# Power_Distribution_-_Front_Lights.net
KiCad netlist of a schematic drawn in Altium Designer
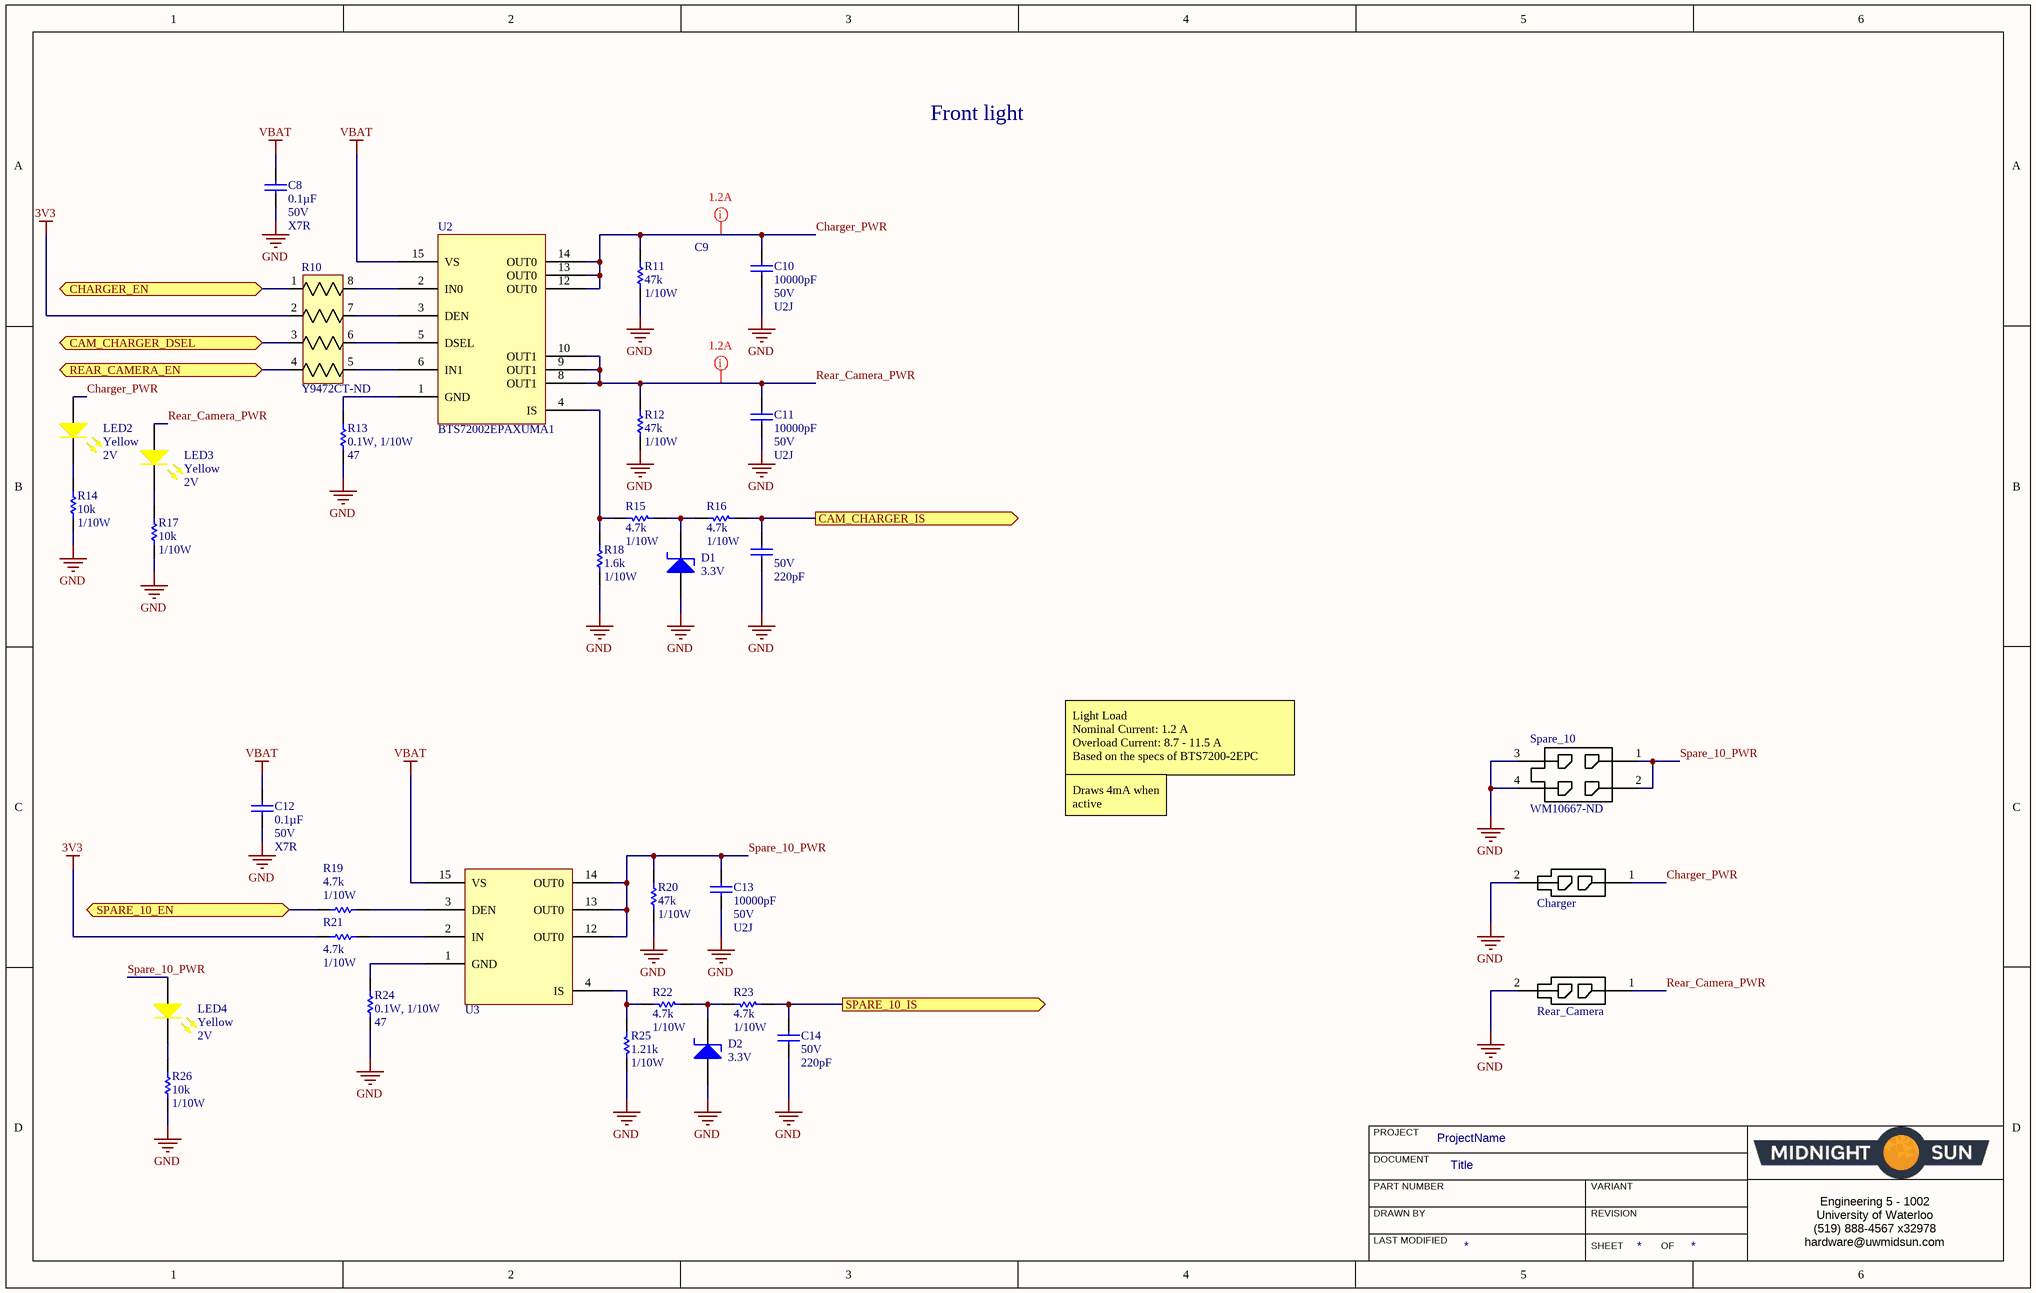
[diagram p0: Power Distribution - Front Lights.SchDoc]

(export (version "E")
  (design (tool "Eeschema 10.0.6"))
  (components
    (comp (ref "C8")
      (value "CAP CER 0.1UF 50V 10% X7R 0603")
      (footprint "CAP, 0603")
      (description "0.10µF ±10% 50V Ceramic Capacitor X7R 0603 (1608 Metric)")
      (fields
        (field (name "TOLERANCE") "±10%")
        (field (name "CAPACITANCE") "0.1µF")
        (field (name "VOLTAGE") "50V")
        (field (name "TEMPERATURE COEFFICIENT") "X7R")
      )
      (libsource (lib "Schematic Diagrams") (part "CAP CER 0.1UF 50V 10% X7R 0603"))
    )
    (comp (ref "C9")
      (value "CAP CER 220PF 50V C0G/NP0 0603")
      (footprint "CAP, 0603")
      (description "220pF ±5% 50V Ceramic Capacitor C0G, NP0 0603 (1608 Metric)")
      (fields
        (field (name "MANUFACTURER") "KEMET")
        (field (name "TOLERANCE") "5%")
        (field (name "VOLTAGE RATING") "50V")
        (field (name "CAPACITANCE") "220pF")
      )
      (libsource (lib "Schematic Diagrams") (part "CAP CER 220PF 50V C0G/NP0 0603"))
    )
    (comp (ref "C10")
      (value "CAP CER 10nF 50V 5% X7R 0603")
      (footprint "CAP, 0603")
      (description "10000pF ±5% 50V Ceramic Capacitor U2J 0603 (1608 Metric)")
      (fields
        (field (name "TOLERANCE") "±5%")
        (field (name "CAPACITANCE") "10000pF")
        (field (name "VOLTAGE") "50V")
        (field (name "TEMPERATURE COEFFICIENT") "U2J")
      )
      (libsource (lib "Schematic Diagrams") (part "CAP CER 10nF 50V 5% X7R 0603"))
    )
    (comp (ref "C11")
      (value "CAP CER 10nF 50V 5% X7R 0603")
      (footprint "CAP, 0603")
      (description "10000pF ±5% 50V Ceramic Capacitor U2J 0603 (1608 Metric)")
      (fields
        (field (name "TOLERANCE") "±5%")
        (field (name "CAPACITANCE") "10000pF")
        (field (name "VOLTAGE") "50V")
        (field (name "TEMPERATURE COEFFICIENT") "U2J")
      )
      (libsource (lib "Schematic Diagrams") (part "CAP CER 10nF 50V 5% X7R 0603"))
    )
    (comp (ref "C12")
      (value "CAP CER 0.1UF 50V 10% X7R 0603")
      (footprint "CAP, 0603")
      (description "0.10µF ±10% 50V Ceramic Capacitor X7R 0603 (1608 Metric)")
      (fields
        (field (name "TOLERANCE") "±10%")
        (field (name "CAPACITANCE") "0.1µF")
        (field (name "VOLTAGE") "50V")
        (field (name "TEMPERATURE COEFFICIENT") "X7R")
      )
      (libsource (lib "Schematic Diagrams") (part "CAP CER 0.1UF 50V 10% X7R 0603"))
    )
    (comp (ref "C13")
      (value "CAP CER 10nF 50V 5% X7R 0603")
      (footprint "CAP, 0603")
      (description "10000pF ±5% 50V Ceramic Capacitor U2J 0603 (1608 Metric)")
      (fields
        (field (name "TOLERANCE") "±5%")
        (field (name "CAPACITANCE") "10000pF")
        (field (name "VOLTAGE") "50V")
        (field (name "TEMPERATURE COEFFICIENT") "U2J")
      )
      (libsource (lib "Schematic Diagrams") (part "CAP CER 10nF 50V 5% X7R 0603"))
    )
    (comp (ref "C14")
      (value "CAP CER 220PF 50V C0G/NP0 0603")
      (footprint "CAP, 0603")
      (description "220pF ±5% 50V Ceramic Capacitor C0G, NP0 0603 (1608 Metric)")
      (fields
        (field (name "MANUFACTURER") "KEMET")
        (field (name "TOLERANCE") "5%")
        (field (name "VOLTAGE RATING") "50V")
        (field (name "CAPACITANCE") "220pF")
      )
      (libsource (lib "Schematic Diagrams") (part "CAP CER 220PF 50V C0G/NP0 0603"))
    )
    (comp (ref "Charger")
      (value "CONN 2POS MICRO-FIT 3mm")
      (footprint "CONN, 2POS MICRO-FIT")
      (description "Connector Header Through Hole 2 position")
      (fields (field (name "MANUFACTURER") "Molex") (field (name "MANUFACTURER PART NUMBER") "43045-0227"))
      (libsource (lib "Schematic Diagrams") (part "CONN 2POS MICRO-FIT 3mm"))
    )
    (comp (ref "D1")
      (value "DIODE ZENER 3.3V 200MW SOD323")
      (footprint "sod-323")
      (description "Zener Diode 3.3V 200mW ±5% Surface Mount SOD-323")
      (fields (field (name "VOLTAGE") "3.3V"))
      (libsource (lib "Schematic Diagrams") (part "DIODE ZENER 3.3V 200MW SOD323"))
    )
    (comp (ref "D2")
      (value "DIODE ZENER 3.3V 200MW SOD323")
      (footprint "sod-323")
      (description "Zener Diode 3.3V 200mW ±5% Surface Mount SOD-323")
      (fields (field (name "VOLTAGE") "3.3V"))
      (libsource (lib "Schematic Diagrams") (part "DIODE ZENER 3.3V 200MW SOD323"))
    )
    (comp (ref "LED2")
      (value "LED YELLOW CLEAR 2.1V 0603")
      (footprint "LED_0603")
      (description "Yellow 590nm LED Indication - Discrete 2V 0603 (1608 Metric)")
      (fields
        (field (name "MANUFACTURER") "Wurth Electronics Inc.")
        (field (name "MANUFACTURER PART NUMBER") "150060YS75000")
        (field (name "COLOR") "Yellow")
        (field (name "VOLTAGE - FORWARD (VF) (TYP)") "2V")
      )
      (libsource (lib "Schematic Diagrams") (part "LED YELLOW CLEAR 2.1V 0603"))
    )
    (comp (ref "LED3")
      (value "LED YELLOW CLEAR 2.1V 0603")
      (footprint "LED_0603")
      (description "Yellow 590nm LED Indication - Discrete 2V 0603 (1608 Metric)")
      (fields
        (field (name "MANUFACTURER") "Wurth Electronics Inc.")
        (field (name "MANUFACTURER PART NUMBER") "150060YS75000")
        (field (name "COLOR") "Yellow")
        (field (name "VOLTAGE - FORWARD (VF) (TYP)") "2V")
      )
      (libsource (lib "Schematic Diagrams") (part "LED YELLOW CLEAR 2.1V 0603"))
    )
    (comp (ref "LED4")
      (value "LED YELLOW CLEAR 2.1V 0603")
      (footprint "LED_0603")
      (description "Yellow 590nm LED Indication - Discrete 2V 0603 (1608 Metric)")
      (fields
        (field (name "MANUFACTURER") "Wurth Electronics Inc.")
        (field (name "MANUFACTURER PART NUMBER") "150060YS75000")
        (field (name "COLOR") "Yellow")
        (field (name "VOLTAGE - FORWARD (VF) (TYP)") "2V")
      )
      (libsource (lib "Schematic Diagrams") (part "LED YELLOW CLEAR 2.1V 0603"))
    )
    (comp (ref "R10")
      (value "RES ARRAY 4 RES 4.7K OHM 1206")
      (footprint "RES ARRAY 4RES 1206")
      (fields (field (name "TOLERANCE") "±5%") (field (name "SUPPLIER PART NUMBER 1") "Y9472CT-ND"))
      (libsource (lib "Schematic Diagrams") (part "RES ARRAY 4 RES 4.7K OHM 1206"))
    )
    (comp (ref "R11")
      (value "RES 47K OHM 1% 1/10W 0603")
      (footprint "RES, 0603")
      (description "47 kOhms ±1% 0.1W, 1/10W Chip Resistor 0603 (1608 Metric) Automotive AEC-Q200 Thick Film")
      (fields
        (field (name "MANUFACTURER") "Panasonic")
        (field (name "MANUFACTURER PART NUMBER") "ERJ3EKF4702V")
        (field (name "RESISTANCE") "47k")
        (field (name "POWER RATING") "1/10W")
      )
      (libsource (lib "Schematic Diagrams") (part "RES 47K OHM 1% 1/10W 0603"))
    )
    (comp (ref "R12")
      (value "RES 47K OHM 1% 1/10W 0603")
      (footprint "RES, 0603")
      (description "47 kOhms ±1% 0.1W, 1/10W Chip Resistor 0603 (1608 Metric) Automotive AEC-Q200 Thick Film")
      (fields
        (field (name "MANUFACTURER") "Panasonic")
        (field (name "MANUFACTURER PART NUMBER") "ERJ3EKF4702V")
        (field (name "RESISTANCE") "47k")
        (field (name "POWER RATING") "1/10W")
      )
      (libsource (lib "Schematic Diagrams") (part "RES 47K OHM 1% 1/10W 0603"))
    )
    (comp (ref "R13")
      (value "RES SMD 47 OHM 1% 1/10W 0603")
      (footprint "RES, 0603")
      (fields
        (field (name "TOLERANCE") "±1%")
        (field (name "POWER (WATTS)") "0.1W, 1/10W")
        (field (name "VALUES") "47")
      )
      (libsource (lib "Schematic Diagrams") (part "RES SMD 47 OHM 1% 1/10W 0603"))
    )
    (comp (ref "R14")
      (value "RES 10K OHM 1% 1/10W 0603")
      (footprint "RES, 0603")
      (description "RES SMD 10K OHM 1% 1/10W 0603")
      (fields
        (field (name "TOLERANCE") "±1%")
        (field (name "RESISTANCE") "10k")
        (field (name "POWER") "1/10W")
      )
      (libsource (lib "Schematic Diagrams") (part "RES 10K OHM 1% 1/10W 0603"))
    )
    (comp (ref "R15")
      (value "RES 4.7K OHM 1% 1/10W 0603")
      (footprint "RES, 0603")
      (description "4.7k Ohm ±1% 0.1W, 1/10W Chip Resistor 0603 (1608 Metric) Moisture Resistant Thick Film")
      (fields
        (field (name "TOLERANCE") "±1%")
        (field (name "RESISTANCE (OHMS)") "4.7k")
        (field (name "POWER (WATTS)") "1/10W")
      )
      (libsource (lib "Schematic Diagrams") (part "RES 4.7K OHM 1% 1/10W 0603"))
    )
    (comp (ref "R16")
      (value "RES 4.7K OHM 1% 1/10W 0603")
      (footprint "RES, 0603")
      (description "4.7k Ohm ±1% 0.1W, 1/10W Chip Resistor 0603 (1608 Metric) Moisture Resistant Thick Film")
      (fields
        (field (name "TOLERANCE") "±1%")
        (field (name "RESISTANCE (OHMS)") "4.7k")
        (field (name "POWER (WATTS)") "1/10W")
      )
      (libsource (lib "Schematic Diagrams") (part "RES 4.7K OHM 1% 1/10W 0603"))
    )
    (comp (ref "R17")
      (value "RES 10K OHM 1% 1/10W 0603")
      (footprint "RES, 0603")
      (description "RES SMD 10K OHM 1% 1/10W 0603")
      (fields
        (field (name "TOLERANCE") "±1%")
        (field (name "RESISTANCE") "10k")
        (field (name "POWER") "1/10W")
      )
      (libsource (lib "Schematic Diagrams") (part "RES 10K OHM 1% 1/10W 0603"))
    )
    (comp (ref "R18")
      (value "RES 1.6K OHM 1% 1/10W 0603")
      (footprint "RES, 0603")
      (description "1.6 kOhms ±1% 0.1W, 1/10W Chip Resistor 0603 (1608 Metric) Moisture Resistant Thick Film")
      (fields
        (field (name "MANUFACTURER") "Yageo")
        (field (name "MANUFACTURER PART NUMBER") "RC0603FR-071K6L")
        (field (name "RESISTANCE") "1.6k")
        (field (name "POWER RATING") "1/10W")
      )
      (libsource (lib "Schematic Diagrams") (part "RES 1.6K OHM 1% 1/10W 0603"))
    )
    (comp (ref "R19")
      (value "RES 4.7K OHM 1% 1/10W 0603")
      (footprint "RES, 0603")
      (description "4.7k Ohm ±1% 0.1W, 1/10W Chip Resistor 0603 (1608 Metric) Moisture Resistant Thick Film")
      (fields
        (field (name "TOLERANCE") "±1%")
        (field (name "RESISTANCE (OHMS)") "4.7k")
        (field (name "POWER (WATTS)") "1/10W")
      )
      (libsource (lib "Schematic Diagrams") (part "RES 4.7K OHM 1% 1/10W 0603"))
    )
    (comp (ref "R20")
      (value "RES 47K OHM 1% 1/10W 0603")
      (footprint "RES, 0603")
      (description "47 kOhms ±1% 0.1W, 1/10W Chip Resistor 0603 (1608 Metric) Automotive AEC-Q200 Thick Film")
      (fields
        (field (name "MANUFACTURER") "Panasonic")
        (field (name "MANUFACTURER PART NUMBER") "ERJ3EKF4702V")
        (field (name "RESISTANCE") "47k")
        (field (name "POWER RATING") "1/10W")
      )
      (libsource (lib "Schematic Diagrams") (part "RES 47K OHM 1% 1/10W 0603"))
    )
    (comp (ref "R21")
      (value "RES 4.7K OHM 1% 1/10W 0603")
      (footprint "RES, 0603")
      (description "4.7k Ohm ±1% 0.1W, 1/10W Chip Resistor 0603 (1608 Metric) Moisture Resistant Thick Film")
      (fields
        (field (name "TOLERANCE") "±1%")
        (field (name "RESISTANCE (OHMS)") "4.7k")
        (field (name "POWER (WATTS)") "1/10W")
      )
      (libsource (lib "Schematic Diagrams") (part "RES 4.7K OHM 1% 1/10W 0603"))
    )
    (comp (ref "R22")
      (value "RES 4.7K OHM 1% 1/10W 0603")
      (footprint "RES, 0603")
      (description "4.7k Ohm ±1% 0.1W, 1/10W Chip Resistor 0603 (1608 Metric) Moisture Resistant Thick Film")
      (fields
        (field (name "TOLERANCE") "±1%")
        (field (name "RESISTANCE (OHMS)") "4.7k")
        (field (name "POWER (WATTS)") "1/10W")
      )
      (libsource (lib "Schematic Diagrams") (part "RES 4.7K OHM 1% 1/10W 0603"))
    )
    (comp (ref "R23")
      (value "RES 4.7K OHM 1% 1/10W 0603")
      (footprint "RES, 0603")
      (description "4.7k Ohm ±1% 0.1W, 1/10W Chip Resistor 0603 (1608 Metric) Moisture Resistant Thick Film")
      (fields
        (field (name "TOLERANCE") "±1%")
        (field (name "RESISTANCE (OHMS)") "4.7k")
        (field (name "POWER (WATTS)") "1/10W")
      )
      (libsource (lib "Schematic Diagrams") (part "RES 4.7K OHM 1% 1/10W 0603"))
    )
    (comp (ref "R24")
      (value "RES SMD 47 OHM 1% 1/10W 0603")
      (footprint "RES, 0603")
      (fields
        (field (name "TOLERANCE") "±1%")
        (field (name "POWER (WATTS)") "0.1W, 1/10W")
        (field (name "VALUES") "47")
      )
      (libsource (lib "Schematic Diagrams") (part "RES SMD 47 OHM 1% 1/10W 0603"))
    )
    (comp (ref "R25")
      (value "RES 1.21K OHM 1% 1/10W 0603")
      (footprint "RES, 0603")
      (description "1.21k Ohm ±1% 0.1W, 1/10W Chip Resistor 0603 (1608 Metric) Moisture Resistant Thick Film")
      (fields
        (field (name "TOLERANCE") "±1%")
        (field (name "RESISTANCE") "1.21k")
        (field (name "POWER") "1/10W")
      )
      (libsource (lib "Schematic Diagrams") (part "RES 1.21K OHM 1% 1/10W 0603"))
    )
    (comp (ref "R26")
      (value "RES 10K OHM 1% 1/10W 0603")
      (footprint "RES, 0603")
      (description "RES SMD 10K OHM 1% 1/10W 0603")
      (fields
        (field (name "TOLERANCE") "±1%")
        (field (name "RESISTANCE") "10k")
        (field (name "POWER") "1/10W")
      )
      (libsource (lib "Schematic Diagrams") (part "RES 10K OHM 1% 1/10W 0603"))
    )
    (comp (ref "Rear_Camera")
      (value "CONN 2POS MICRO-FIT 3mm")
      (footprint "CONN, 2POS MICRO-FIT")
      (description "Connector Header Through Hole 2 position")
      (fields (field (name "MANUFACTURER") "Molex") (field (name "MANUFACTURER PART NUMBER") "43045-0227"))
      (libsource (lib "Schematic Diagrams") (part "CONN 2POS MICRO-FIT 3mm"))
    )
    (comp (ref "Spare_10")
      (value "CONN 4POS MICRO-FIT 3mm")
      (footprint "CONN 4POS MICROFIT (2x2)")
      (fields
        (field (name "MANUFACTURER") "Molex, LLC")
        (field (name "MANUFACTURER PART NUMBER") "430450427")
        (field (name "SUPPLIER PART NUMBER 1") "WM10667-ND")
      )
      (libsource (lib "Schematic Diagrams") (part "CONN 4POS MICRO-FIT 3mm"))
    )
    (comp (ref "U2")
      (value "IC LOAD SWITCH BTS7200-2EPA PG-TSDSO-14_1")
      (footprint "IC LOAD SWITCH PG-TSDSO-14-22")
      (description "Power Switch/Driver 1:1 N-Channel 1.2A PG-TSDSO-14-22")
      (fields
        (field (name "MANUFACTURER") "Infineon")
        (field (name "MANUFACTURER PART NUMBER") "BTS72002EPAXUMA1")
      )
      (libsource (lib "Schematic Diagrams") (part "IC LOAD SWITCH BTS7200-2EPA PG-TSDSO-14_1"))
    )
    (comp (ref "U3")
      (value "IC LOAD SWITCH BTS70401EPA PG-TSDSO-14-22")
      (footprint "IC LOAD SWITCH PG-TSDSO-14-22")
      (description "Power Switch/Driver 1:1 N-Channel 4.5A PG-TSDSO-14-22")
      (fields
        (field (name "MANUFACTURER") "Infineon")
        (field (name "MANUFACTURER PART NUMBER") "BTS70401EPAXUMA1")
      )
      (libsource (lib "Schematic Diagrams") (part "IC LOAD SWITCH BTS70401EPA PG-TSDSO-14-22"))
    )
  )
  (nets
    (net (code "1") (name "/CAM_CHARGER_DSEL") (class "Default")
      (node (ref "R10") (pin "3") (pinfunction "3_3") (pintype "passive"))
    )
    (net (code "2") (name "/CAM_CHARGER_IS") (class "Default")
      (node (ref "C9") (pin "1") (pinfunction "1_1") (pintype "passive"))
      (node (ref "R16") (pin "1") (pinfunction "1_1") (pintype "passive"))
    )
    (net (code "3") (name "/CHARGER_EN") (class "Default")
      (node (ref "R10") (pin "1") (pinfunction "1_1") (pintype "passive"))
    )
    (net (code "4") (name "/Charger_PWR") (class "Default")
      (node (ref "C10") (pin "1") (pinfunction "1_1") (pintype "passive"))
      (node (ref "Charger") (pin "1") (pinfunction "1_1") (pintype "passive"))
      (node (ref "LED2") (pin "1") (pinfunction "A_1") (pintype "passive"))
      (node (ref "R11") (pin "1") (pinfunction "1_1") (pintype "passive"))
      (node (ref "U2") (pin "12") (pinfunction "OUT0_12") (pintype "passive"))
      (node (ref "U2") (pin "13") (pinfunction "OUT0_13") (pintype "passive"))
      (node (ref "U2") (pin "14") (pinfunction "OUT0_14") (pintype "passive"))
    )
    (net (code "5") (name "/REAR_CAMERA_EN") (class "Default")
      (node (ref "R10") (pin "4") (pinfunction "4_4") (pintype "passive"))
    )
    (net (code "6") (name "/Rear_Camera_PWR") (class "Default")
      (node (ref "C11") (pin "1") (pinfunction "1_1") (pintype "passive"))
      (node (ref "LED3") (pin "1") (pinfunction "A_1") (pintype "passive"))
      (node (ref "R12") (pin "1") (pinfunction "1_1") (pintype "passive"))
      (node (ref "Rear_Camera") (pin "1") (pinfunction "1_1") (pintype "passive"))
      (node (ref "U2") (pin "10") (pinfunction "OUT1_10") (pintype "passive"))
      (node (ref "U2") (pin "8") (pinfunction "OUT1_8") (pintype "passive"))
      (node (ref "U2") (pin "9") (pinfunction "OUT1_9") (pintype "passive"))
    )
    (net (code "7") (name "/SPARE_10_EN") (class "Default")
      (node (ref "R19") (pin "1") (pinfunction "1_1") (pintype "passive"))
    )
    (net (code "8") (name "/SPARE_10_IS") (class "Default")
      (node (ref "C14") (pin "1") (pinfunction "1_1") (pintype "passive"))
      (node (ref "R23") (pin "1") (pinfunction "1_1") (pintype "passive"))
    )
    (net (code "9") (name "/Spare_10_PWR") (class "Default")
      (node (ref "C13") (pin "1") (pinfunction "1_1") (pintype "passive"))
      (node (ref "LED4") (pin "1") (pinfunction "A_1") (pintype "passive"))
      (node (ref "R20") (pin "1") (pinfunction "1_1") (pintype "passive"))
      (node (ref "Spare_10") (pin "1") (pinfunction "1_1") (pintype "passive"))
      (node (ref "Spare_10") (pin "2") (pinfunction "2_2") (pintype "passive"))
      (node (ref "U3") (pin "12") (pinfunction "OUT0_12") (pintype "passive"))
      (node (ref "U3") (pin "13") (pinfunction "OUT0_13") (pintype "passive"))
      (node (ref "U3") (pin "14") (pinfunction "OUT0_14") (pintype "passive"))
    )
    (net (code "10") (name "3V3") (class "Default")
      (node (ref "R10") (pin "2") (pinfunction "2_2") (pintype "passive"))
      (node (ref "R21") (pin "1") (pinfunction "1_1") (pintype "passive"))
    )
    (net (code "11") (name "GND") (class "Default")
      (node (ref "C10") (pin "2") (pinfunction "2_2") (pintype "passive"))
      (node (ref "C11") (pin "2") (pinfunction "2_2") (pintype "passive"))
      (node (ref "C12") (pin "2") (pinfunction "2_2") (pintype "passive"))
      (node (ref "C13") (pin "2") (pinfunction "2_2") (pintype "passive"))
      (node (ref "C14") (pin "2") (pinfunction "2_2") (pintype "passive"))
      (node (ref "C8") (pin "2") (pinfunction "2_2") (pintype "passive"))
      (node (ref "C9") (pin "2") (pinfunction "2_2") (pintype "passive"))
      (node (ref "Charger") (pin "2") (pinfunction "2_2") (pintype "passive"))
      (node (ref "D1") (pin "1") (pinfunction "A_1") (pintype "passive"))
      (node (ref "D2") (pin "1") (pinfunction "A_1") (pintype "passive"))
      (node (ref "R11") (pin "2") (pinfunction "2_2") (pintype "passive"))
      (node (ref "R12") (pin "2") (pinfunction "2_2") (pintype "passive"))
      (node (ref "R13") (pin "2") (pinfunction "2_2") (pintype "passive"))
      (node (ref "R14") (pin "2") (pinfunction "2_2") (pintype "passive"))
      (node (ref "R17") (pin "2") (pinfunction "2_2") (pintype "passive"))
      (node (ref "R18") (pin "2") (pinfunction "2_2") (pintype "passive"))
      (node (ref "R20") (pin "2") (pinfunction "2_2") (pintype "passive"))
      (node (ref "R24") (pin "2") (pinfunction "2_2") (pintype "passive"))
      (node (ref "R25") (pin "2") (pinfunction "2_2") (pintype "passive"))
      (node (ref "R26") (pin "2") (pinfunction "2_2") (pintype "passive"))
      (node (ref "Rear_Camera") (pin "2") (pinfunction "2_2") (pintype "passive"))
      (node (ref "Spare_10") (pin "3") (pinfunction "3_3") (pintype "passive"))
      (node (ref "Spare_10") (pin "4") (pinfunction "4_4") (pintype "passive"))
    )
    (net (code "12") (name "Net-(D1-K)") (class "Default")
      (node (ref "D1") (pin "2") (pinfunction "K_2") (pintype "passive"))
      (node (ref "R15") (pin "1") (pinfunction "1_1") (pintype "passive"))
      (node (ref "R16") (pin "2") (pinfunction "2_2") (pintype "passive"))
    )
    (net (code "13") (name "Net-(D2-K)") (class "Default")
      (node (ref "D2") (pin "2") (pinfunction "K_2") (pintype "passive"))
      (node (ref "R22") (pin "1") (pinfunction "1_1") (pintype "passive"))
      (node (ref "R23") (pin "2") (pinfunction "2_2") (pintype "passive"))
    )
    (net (code "14") (name "Net-(LED2-K)") (class "Default")
      (node (ref "LED2") (pin "2") (pinfunction "K_2") (pintype "passive"))
      (node (ref "R14") (pin "1") (pinfunction "1_1") (pintype "passive"))
    )
    (net (code "15") (name "Net-(LED3-K)") (class "Default")
      (node (ref "LED3") (pin "2") (pinfunction "K_2") (pintype "passive"))
      (node (ref "R17") (pin "1") (pinfunction "1_1") (pintype "passive"))
    )
    (net (code "16") (name "Net-(LED4-K)") (class "Default")
      (node (ref "LED4") (pin "2") (pinfunction "K_2") (pintype "passive"))
      (node (ref "R26") (pin "1") (pinfunction "1_1") (pintype "passive"))
    )
    (net (code "17") (name "Net-(U2-DEN)") (class "Default")
      (node (ref "R10") (pin "7") (pinfunction "7_7") (pintype "passive"))
      (node (ref "U2") (pin "3") (pinfunction "DEN_3") (pintype "passive"))
    )
    (net (code "18") (name "Net-(U2-DSEL)") (class "Default")
      (node (ref "R10") (pin "6") (pinfunction "6_6") (pintype "passive"))
      (node (ref "U2") (pin "5") (pinfunction "DSEL_5") (pintype "passive"))
    )
    (net (code "19") (name "Net-(U2-GND)") (class "Default")
      (node (ref "R13") (pin "1") (pinfunction "1_1") (pintype "passive"))
      (node (ref "U2") (pin "1") (pinfunction "GND_1") (pintype "passive"))
    )
    (net (code "20") (name "Net-(U2-IN0)") (class "Default")
      (node (ref "R10") (pin "8") (pinfunction "8_8") (pintype "passive"))
      (node (ref "U2") (pin "2") (pinfunction "IN0_2") (pintype "passive"))
    )
    (net (code "21") (name "Net-(U2-IN1)") (class "Default")
      (node (ref "R10") (pin "5") (pinfunction "5_5") (pintype "passive"))
      (node (ref "U2") (pin "6") (pinfunction "IN1_6") (pintype "passive"))
    )
    (net (code "22") (name "Net-(U2-IS)") (class "Default")
      (node (ref "R15") (pin "2") (pinfunction "2_2") (pintype "passive"))
      (node (ref "R18") (pin "1") (pinfunction "1_1") (pintype "passive"))
      (node (ref "U2") (pin "4") (pinfunction "IS_4") (pintype "passive"))
    )
    (net (code "23") (name "Net-(U3-DEN)") (class "Default")
      (node (ref "R19") (pin "2") (pinfunction "2_2") (pintype "passive"))
      (node (ref "U3") (pin "3") (pinfunction "DEN_3") (pintype "passive"))
    )
    (net (code "24") (name "Net-(U3-GND)") (class "Default")
      (node (ref "R24") (pin "1") (pinfunction "1_1") (pintype "passive"))
      (node (ref "U3") (pin "1") (pinfunction "GND_1") (pintype "passive"))
    )
    (net (code "25") (name "Net-(U3-IN)") (class "Default")
      (node (ref "R21") (pin "2") (pinfunction "2_2") (pintype "passive"))
      (node (ref "U3") (pin "2") (pinfunction "IN_2") (pintype "passive"))
    )
    (net (code "26") (name "Net-(U3-IS)") (class "Default")
      (node (ref "R22") (pin "2") (pinfunction "2_2") (pintype "passive"))
      (node (ref "R25") (pin "1") (pinfunction "1_1") (pintype "passive"))
      (node (ref "U3") (pin "4") (pinfunction "IS_4") (pintype "passive"))
    )
    (net (code "27") (name "VBAT") (class "Default")
      (node (ref "C12") (pin "1") (pinfunction "1_1") (pintype "passive"))
      (node (ref "C8") (pin "1") (pinfunction "1_1") (pintype "passive"))
      (node (ref "U2") (pin "15") (pinfunction "VS_15") (pintype "passive"))
      (node (ref "U3") (pin "15") (pinfunction "VS_15") (pintype "passive"))
    )
  )
)
